# Sense.net
KiCad netlist of a schematic drawn in Altium Designer
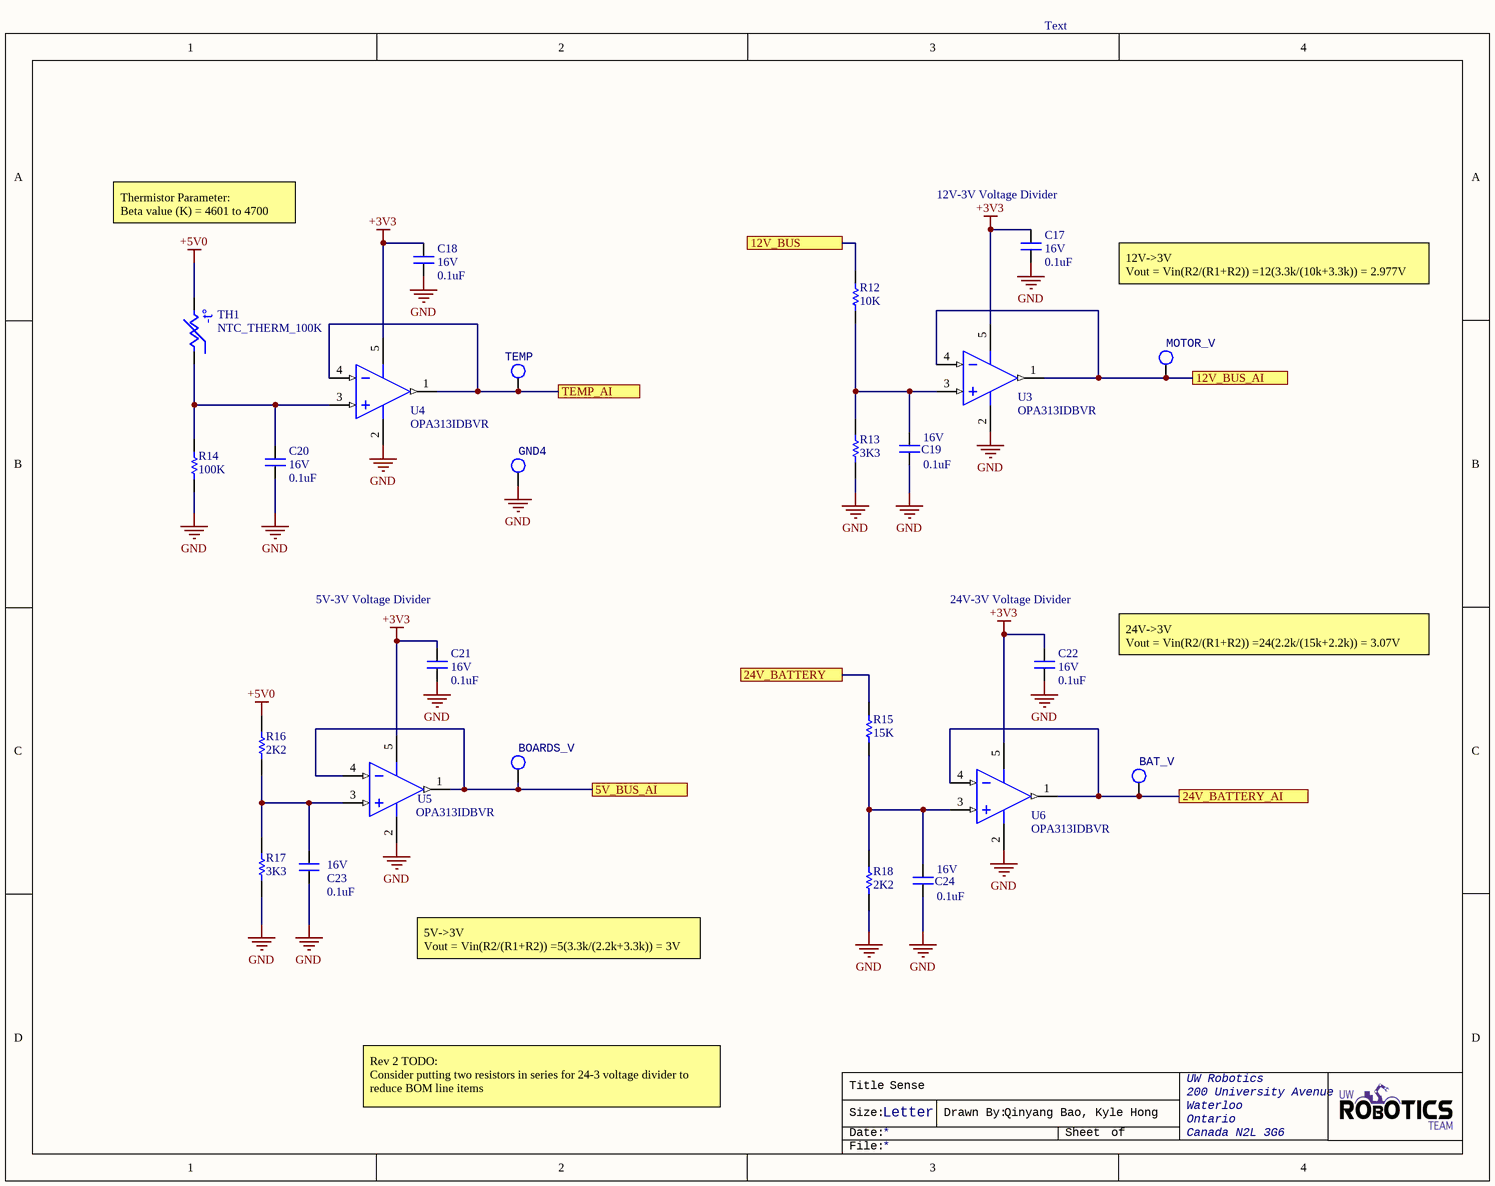
[diagram p0: Sense.SchDoc]

(export (version "E")
  (design (tool "Eeschema 10.0.6"))
  (components
    (comp (ref "BAT_V")
      (value "TESTPOINT_LOOP")
      (footprint "TESTPOINT_LOOP")
      (description "Loop testpoint through-hole pad")
      (fields (field (name "MANUFACTURER") "Keystone Electronics"))
      (libsource (lib "UWRT_Schematic_Library_2020") (part "TESTPOINT_LOOP"))
    )
    (comp (ref "BOARDS_V")
      (value "TESTPOINT_LOOP")
      (footprint "TESTPOINT_LOOP")
      (description "Loop testpoint through-hole pad")
      (fields (field (name "MANUFACTURER") "Keystone Electronics"))
      (libsource (lib "UWRT_Schematic_Library_2020") (part "TESTPOINT_LOOP"))
    )
    (comp (ref "C17")
      (value "0.1uF")
      (footprint "CAPC0603(1608)55_N")
      (description "CAP CER 0.1UF 16V X7R 0603")
      (fields
        (field (name "MPN") "CC0603KRX7R7BB104")
        (field (name "MANUFACTURER") "Yageo")
        (field (name "VOLTAGE RATING") "16V")
      )
      (libsource (lib "UWRT_Schematic_Library_2020") (part "CAP_0.1uF_16V_0603"))
    )
    (comp (ref "C18")
      (value "0.1uF")
      (footprint "CAPC0603(1608)55_N")
      (description "CAP CER 0.1UF 16V X7R 0603")
      (fields
        (field (name "MPN") "CC0603KRX7R7BB104")
        (field (name "MANUFACTURER") "Yageo")
        (field (name "VOLTAGE RATING") "16V")
      )
      (libsource (lib "UWRT_Schematic_Library_2020") (part "CAP_0.1uF_16V_0603"))
    )
    (comp (ref "C19")
      (value "0.1uF")
      (footprint "CAPC0603(1608)55_N")
      (description "CAP CER 0.1UF 16V X7R 0603")
      (fields
        (field (name "MPN") "CC0603KRX7R7BB104")
        (field (name "MANUFACTURER") "Yageo")
        (field (name "VOLTAGE RATING") "16V")
      )
      (libsource (lib "UWRT_Schematic_Library_2020") (part "CAP_0.1uF_16V_0603"))
    )
    (comp (ref "C20")
      (value "0.1uF")
      (footprint "CAPC0603(1608)55_N")
      (description "CAP CER 0.1UF 16V X7R 0603")
      (fields
        (field (name "MPN") "CC0603KRX7R7BB104")
        (field (name "MANUFACTURER") "Yageo")
        (field (name "VOLTAGE RATING") "16V")
      )
      (libsource (lib "UWRT_Schematic_Library_2020") (part "CAP_0.1uF_16V_0603"))
    )
    (comp (ref "C21")
      (value "0.1uF")
      (footprint "CAPC0603(1608)55_N")
      (description "CAP CER 0.1UF 16V X7R 0603")
      (fields
        (field (name "MPN") "CC0603KRX7R7BB104")
        (field (name "MANUFACTURER") "Yageo")
        (field (name "VOLTAGE RATING") "16V")
      )
      (libsource (lib "UWRT_Schematic_Library_2020") (part "CAP_0.1uF_16V_0603"))
    )
    (comp (ref "C22")
      (value "0.1uF")
      (footprint "CAPC0603(1608)55_N")
      (description "CAP CER 0.1UF 16V X7R 0603")
      (fields
        (field (name "MPN") "CC0603KRX7R7BB104")
        (field (name "MANUFACTURER") "Yageo")
        (field (name "VOLTAGE RATING") "16V")
      )
      (libsource (lib "UWRT_Schematic_Library_2020") (part "CAP_0.1uF_16V_0603"))
    )
    (comp (ref "C23")
      (value "0.1uF")
      (footprint "CAPC0603(1608)55_N")
      (description "CAP CER 0.1UF 16V X7R 0603")
      (fields
        (field (name "MPN") "CC0603KRX7R7BB104")
        (field (name "MANUFACTURER") "Yageo")
        (field (name "VOLTAGE RATING") "16V")
      )
      (libsource (lib "UWRT_Schematic_Library_2020") (part "CAP_0.1uF_16V_0603"))
    )
    (comp (ref "C24")
      (value "0.1uF")
      (footprint "CAPC0603(1608)55_N")
      (description "CAP CER 0.1UF 16V X7R 0603")
      (fields
        (field (name "MPN") "CC0603KRX7R7BB104")
        (field (name "MANUFACTURER") "Yageo")
        (field (name "VOLTAGE RATING") "16V")
      )
      (libsource (lib "UWRT_Schematic_Library_2020") (part "CAP_0.1uF_16V_0603"))
    )
    (comp (ref "GND4")
      (value "TESTPOINT_LOOP")
      (footprint "TESTPOINT_LOOP")
      (description "Loop testpoint through-hole pad")
      (fields (field (name "MANUFACTURER") "Keystone Electronics"))
      (libsource (lib "UWRT_Schematic_Library_2020") (part "TESTPOINT_LOOP"))
    )
    (comp (ref "MOTOR_V")
      (value "TESTPOINT_LOOP")
      (footprint "TESTPOINT_LOOP")
      (description "Loop testpoint through-hole pad")
      (fields (field (name "MANUFACTURER") "Keystone Electronics"))
      (libsource (lib "UWRT_Schematic_Library_2020") (part "TESTPOINT_LOOP"))
    )
    (comp (ref "R12")
      (value "10K")
      (footprint "RESC0603(1608)_N")
      (description "RES SMD 10K OHM 5% 1/10W 0603")
      (fields (field (name "TOLERANCE") "5%") (field (name "MANUFACTURER") "Yageo"))
      (libsource (lib "UWRT_Schematic_Library_2020") (part "RES_10K_0603"))
    )
    (comp (ref "R13")
      (value "3K3")
      (footprint "RESC0603(1608)_N")
      (description "RES SMD 3.3K OHM 5% 1/10W 0603")
      (fields (field (name "TOLERANCE") "5%") (field (name "MANUFACTURER") "Yageo"))
      (libsource (lib "UWRT_Schematic_Library_2020") (part "RES_3K3_0603"))
    )
    (comp (ref "R14")
      (value "100K")
      (footprint "RESC0603(1608)_N")
      (description "RES SMD 100K OHM 5% 1/10W 0603")
      (fields (field (name "TOLERANCE") "5%") (field (name "MANUFACTURER") "Yageo"))
      (libsource (lib "UWRT_Schematic_Library_2020") (part "RES_100K_0603"))
    )
    (comp (ref "R15")
      (value "15K")
      (footprint "RESC0603(1608)_N")
      (description "RES SMD 15K OHM 5% 1/10W 0603")
      (fields (field (name "TOLERANCE") "5%") (field (name "Comment") "RES_15K_0603"))
      (libsource (lib "UWRT_Schematic_Library_2020") (part "RES_15K_0603"))
    )
    (comp (ref "R16")
      (value "2K2")
      (footprint "RESC0603(1608)_N")
      (description "RES SMD 2.2K OHM 1% 1/10W 0603")
      (fields (field (name "TOLERANCE") "1%") (field (name "MANUFACTURER") "Yageo"))
      (libsource (lib "UWRT_Schematic_Library_2020") (part "RES_2K2_0603"))
    )
    (comp (ref "R17")
      (value "3K3")
      (footprint "RESC0603(1608)_N")
      (description "RES SMD 3.3K OHM 5% 1/10W 0603")
      (fields (field (name "TOLERANCE") "5%") (field (name "MANUFACTURER") "Yageo"))
      (libsource (lib "UWRT_Schematic_Library_2020") (part "RES_3K3_0603"))
    )
    (comp (ref "R18")
      (value "2K2")
      (footprint "RESC0603(1608)_N")
      (description "RES SMD 2.2K OHM 1% 1/10W 0603")
      (fields (field (name "TOLERANCE") "1%") (field (name "MANUFACTURER") "Yageo"))
      (libsource (lib "UWRT_Schematic_Library_2020") (part "RES_2K2_0603"))
    )
    (comp (ref "TEMP")
      (value "TESTPOINT_LOOP")
      (footprint "TESTPOINT_LOOP")
      (description "Loop testpoint through-hole pad")
      (fields (field (name "MANUFACTURER") "Keystone Electronics"))
      (libsource (lib "UWRT_Schematic_Library_2020") (part "TESTPOINT_LOOP"))
    )
    (comp (ref "TH1")
      (value "NTC_THERM_100K")
      (footprint "RESC0603(1608)_N")
      (description "THERM NTC 100KOHM 4700K 0603")
      (fields (field (name "MPN") "ERT-J1VV104J") (field (name "MANUFACTURER") "Panasonic"))
      (libsource (lib "UWRT_Schematic_Library_2020") (part "NTC_THERM_100K"))
    )
    (comp (ref "U3")
      (value "OPA313IDBVR")
      (footprint "DBV0005A_M")
      (description "IC OPAMP GP 1 CIRCUIT SOT23-5")
      (fields (field (name "MANUFACTURER") "Texas Instruments"))
      (libsource (lib "UWRT_Schematic_Library_2020") (part "OPAMP"))
    )
    (comp (ref "U4")
      (value "OPA313IDBVR")
      (footprint "DBV0005A_M")
      (description "IC OPAMP GP 1 CIRCUIT SOT23-5")
      (fields (field (name "MANUFACTURER") "Texas Instruments"))
      (libsource (lib "UWRT_Schematic_Library_2020") (part "OPAMP"))
    )
    (comp (ref "U5")
      (value "OPA313IDBVR")
      (footprint "DBV0005A_M")
      (description "IC OPAMP GP 1 CIRCUIT SOT23-5")
      (fields (field (name "MANUFACTURER") "Texas Instruments"))
      (libsource (lib "UWRT_Schematic_Library_2020") (part "OPAMP"))
    )
    (comp (ref "U6")
      (value "OPA313IDBVR")
      (footprint "DBV0005A_M")
      (description "IC OPAMP GP 1 CIRCUIT SOT23-5")
      (fields (field (name "MANUFACTURER") "Texas Instruments"))
      (libsource (lib "UWRT_Schematic_Library_2020") (part "OPAMP"))
    )
  )
  (nets
    (net (code "1") (name "+3V3") (class "Default")
      (node (ref "C17") (pin "2") (pinfunction "2_2") (pintype "passive"))
      (node (ref "C18") (pin "1") (pinfunction "1_1") (pintype "passive"))
      (node (ref "C21") (pin "2") (pinfunction "2_2") (pintype "passive"))
      (node (ref "C22") (pin "2") (pinfunction "2_2") (pintype "passive"))
      (node (ref "U3") (pin "5") (pinfunction "V+_5") (pintype "power_in"))
      (node (ref "U4") (pin "5") (pinfunction "V+_5") (pintype "power_in"))
      (node (ref "U5") (pin "5") (pinfunction "V+_5") (pintype "power_in"))
      (node (ref "U6") (pin "5") (pinfunction "V+_5") (pintype "power_in"))
    )
    (net (code "2") (name "+5V0") (class "Default")
      (node (ref "R16") (pin "2") (pinfunction "2_2") (pintype "passive"))
      (node (ref "TH1") (pin "1") (pinfunction "1_1") (pintype "passive"))
    )
    (net (code "3") (name "/5V_BUS_AI") (class "Default")
      (node (ref "BOARDS_V") (pin "1") (pintype "passive"))
      (node (ref "U5") (pin "1") (pinfunction "OUT_1") (pintype "output"))
      (node (ref "U5") (pin "4") (pinfunction "IN-_4") (pintype "input"))
    )
    (net (code "4") (name "/12V_BUS") (class "Default")
      (node (ref "R12") (pin "2") (pinfunction "2_2") (pintype "passive"))
    )
    (net (code "5") (name "/12V_BUS_AI") (class "Default")
      (node (ref "MOTOR_V") (pin "1") (pintype "passive"))
      (node (ref "U3") (pin "1") (pinfunction "OUT_1") (pintype "output"))
      (node (ref "U3") (pin "4") (pinfunction "IN-_4") (pintype "input"))
    )
    (net (code "6") (name "/24V_BATTERY") (class "Default")
      (node (ref "R15") (pin "2") (pinfunction "2_2") (pintype "passive"))
    )
    (net (code "7") (name "/24V_BATTERY_AI") (class "Default")
      (node (ref "BAT_V") (pin "1") (pintype "passive"))
      (node (ref "U6") (pin "1") (pinfunction "OUT_1") (pintype "output"))
      (node (ref "U6") (pin "4") (pinfunction "IN-_4") (pintype "input"))
    )
    (net (code "8") (name "/TEMP_AI") (class "Default")
      (node (ref "TEMP") (pin "1") (pintype "passive"))
      (node (ref "U4") (pin "1") (pinfunction "OUT_1") (pintype "output"))
      (node (ref "U4") (pin "4") (pinfunction "IN-_4") (pintype "input"))
    )
    (net (code "9") (name "GND") (class "Default")
      (node (ref "C17") (pin "1") (pinfunction "1_1") (pintype "passive"))
      (node (ref "C18") (pin "2") (pinfunction "2_2") (pintype "passive"))
      (node (ref "C19") (pin "1") (pinfunction "1_1") (pintype "passive"))
      (node (ref "C20") (pin "1") (pinfunction "1_1") (pintype "passive"))
      (node (ref "C21") (pin "1") (pinfunction "1_1") (pintype "passive"))
      (node (ref "C22") (pin "1") (pinfunction "1_1") (pintype "passive"))
      (node (ref "C23") (pin "1") (pinfunction "1_1") (pintype "passive"))
      (node (ref "C24") (pin "1") (pinfunction "1_1") (pintype "passive"))
      (node (ref "GND4") (pin "1") (pintype "passive"))
      (node (ref "R13") (pin "1") (pinfunction "1_1") (pintype "passive"))
      (node (ref "R14") (pin "1") (pinfunction "1_1") (pintype "passive"))
      (node (ref "R17") (pin "1") (pinfunction "1_1") (pintype "passive"))
      (node (ref "R18") (pin "1") (pinfunction "1_1") (pintype "passive"))
      (node (ref "U3") (pin "2") (pinfunction "V-_2") (pintype "power_in"))
      (node (ref "U4") (pin "2") (pinfunction "V-_2") (pintype "power_in"))
      (node (ref "U5") (pin "2") (pinfunction "V-_2") (pintype "power_in"))
      (node (ref "U6") (pin "2") (pinfunction "V-_2") (pintype "power_in"))
    )
    (net (code "10") (name "Net-(U3-IN+)") (class "Default")
      (node (ref "C19") (pin "2") (pinfunction "2_2") (pintype "passive"))
      (node (ref "R12") (pin "1") (pinfunction "1_1") (pintype "passive"))
      (node (ref "R13") (pin "2") (pinfunction "2_2") (pintype "passive"))
      (node (ref "U3") (pin "3") (pinfunction "IN+_3") (pintype "input"))
    )
    (net (code "11") (name "Net-(U4-IN+)") (class "Default")
      (node (ref "C20") (pin "2") (pinfunction "2_2") (pintype "passive"))
      (node (ref "R14") (pin "2") (pinfunction "2_2") (pintype "passive"))
      (node (ref "TH1") (pin "2") (pinfunction "2_2") (pintype "passive"))
      (node (ref "U4") (pin "3") (pinfunction "IN+_3") (pintype "input"))
    )
    (net (code "12") (name "Net-(U5-IN+)") (class "Default")
      (node (ref "C23") (pin "2") (pinfunction "2_2") (pintype "passive"))
      (node (ref "R16") (pin "1") (pinfunction "1_1") (pintype "passive"))
      (node (ref "R17") (pin "2") (pinfunction "2_2") (pintype "passive"))
      (node (ref "U5") (pin "3") (pinfunction "IN+_3") (pintype "input"))
    )
    (net (code "13") (name "Net-(U6-IN+)") (class "Default")
      (node (ref "C24") (pin "2") (pinfunction "2_2") (pintype "passive"))
      (node (ref "R15") (pin "1") (pinfunction "1_1") (pintype "passive"))
      (node (ref "R18") (pin "2") (pinfunction "2_2") (pintype "passive"))
      (node (ref "U6") (pin "3") (pinfunction "IN+_3") (pintype "input"))
    )
  )
)
